# MercurialSDR_PWR.net
KiCad netlist of a schematic drawn in Altium Designer
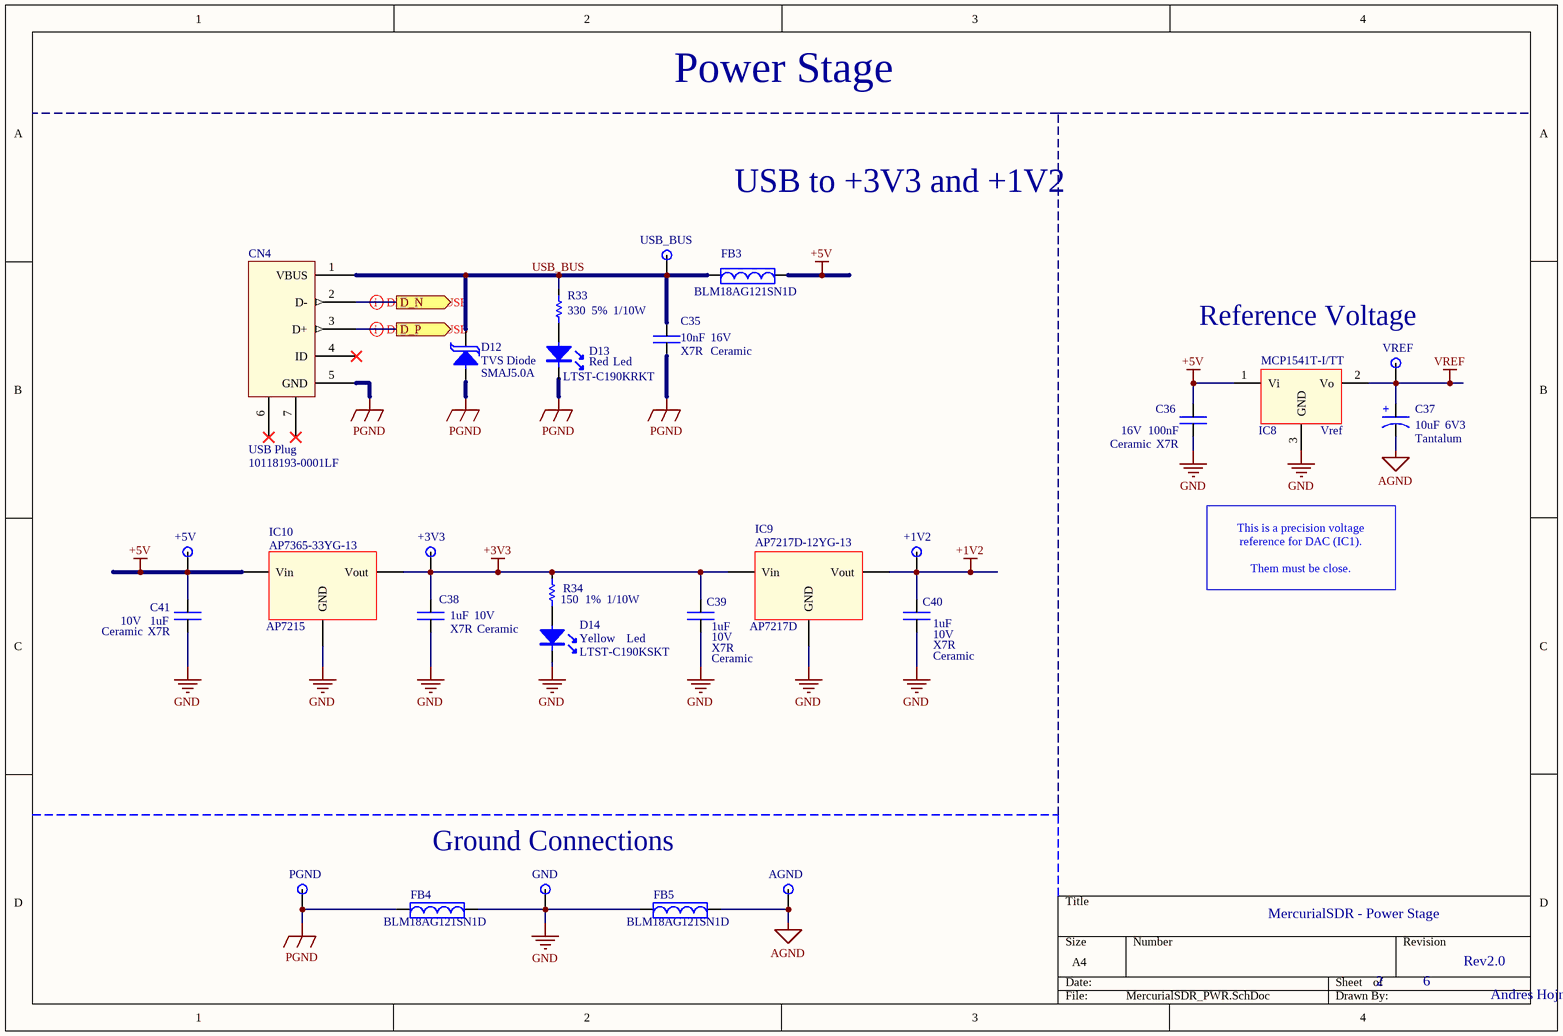
[diagram p0: MercurialSDR_PWR.SchDoc]

(export (version "E")
  (design (tool "Eeschema 10.0.6"))
  (components
    (comp (ref "C35")
      (value "10nF")
      (footprint "CAP_0603")
      (description "Capacitor no polarizado")
      (fields
        (field (name "TEMP COEF") "X7R")
        (field (name "PART NUMBER") "CC0603KRX7R7BB103")
        (field (name "VR") "16V")
        (field (name "MATERIAL") "Ceramic")
        (field (name "Comment") "Capacitor")
      )
      (libsource (lib "MercurialSDR") (part "Cap"))
    )
    (comp (ref "C36")
      (value "100nF")
      (footprint "CAP_0603")
      (description "Capacitor no polarizado")
      (fields
        (field (name "TEMP COEF") "X7R")
        (field (name "PART NUMBER") "CL10B104KO8NNNC")
        (field (name "VR") "16V")
        (field (name "MATERIAL") "Ceramic")
        (field (name "Comment") "Capacitor")
      )
      (libsource (lib "MercurialSDR") (part "Cap"))
    )
    (comp (ref "C37")
      (value "10uF")
      (footprint "CAP_TANT_1206")
      (description "Capacitor polarizado")
      (fields
        (field (name "PART NUMBER") "TAJA106K006RNJ")
        (field (name "VR") "6V3")
        (field (name "MATERIAL") "Tantalum")
        (field (name "Comment") "Capacitor Polarizado")
      )
      (libsource (lib "MercurialSDR") (part "Cap Pol"))
    )
    (comp (ref "C38")
      (value "1uF")
      (footprint "CAP_0603")
      (description "Capacitor no polarizado")
      (fields
        (field (name "TEMP COEF") "X7R")
        (field (name "PART NUMBER") "CL10B105KP8NNNC")
        (field (name "VR") "10V")
        (field (name "MATERIAL") "Ceramic")
        (field (name "Comment") "Capacitor")
      )
      (libsource (lib "MercurialSDR") (part "Cap"))
    )
    (comp (ref "C39")
      (value "1uF")
      (footprint "CAP_0603")
      (description "Capacitor no polarizado")
      (fields
        (field (name "TEMP COEF") "X7R")
        (field (name "PART NUMBER") "CL10B105KP8NNNC")
        (field (name "VR") "10V")
        (field (name "MATERIAL") "Ceramic")
        (field (name "Comment") "Capacitor")
      )
      (libsource (lib "MercurialSDR") (part "Cap"))
    )
    (comp (ref "C40")
      (value "1uF")
      (footprint "CAP_0603")
      (description "Capacitor no polarizado")
      (fields
        (field (name "TEMP COEF") "X7R")
        (field (name "PART NUMBER") "CL10B105KP8NNNC")
        (field (name "VR") "10V")
        (field (name "MATERIAL") "Ceramic")
        (field (name "Comment") "Capacitor")
      )
      (libsource (lib "MercurialSDR") (part "Cap"))
    )
    (comp (ref "C41")
      (value "1uF")
      (footprint "CAP_0603")
      (description "Capacitor no polarizado")
      (fields
        (field (name "TEMP COEF") "X7R")
        (field (name "PART NUMBER") "CL10B105KP8NNNC")
        (field (name "VR") "10V")
        (field (name "MATERIAL") "Ceramic")
        (field (name "Comment") "Capacitor")
      )
      (libsource (lib "MercurialSDR") (part "Cap"))
    )
    (comp (ref "CN4")
      (value "USB Plug")
      (footprint "USB_Micro")
      (fields (field (name "PART NUMBER") "10118193-0001LF"))
      (libsource (lib "MercurialSDR") (part "USB Plug"))
    )
    (comp (ref "D12")
      (value "TVS Diode")
      (footprint "DO-214AC")
      (description "TVS (Supresor de transitorios)")
      (fields (field (name "PART NUMBER") "SMAJ5.0A"))
      (libsource (lib "MercurialSDR") (part "TVS_DIODE"))
    )
    (comp (ref "D13")
      (value "Led")
      (footprint "LED_0603")
      (fields (field (name "COLOR") "Red") (field (name "PART NUMBER") "LTST-C190KRKT"))
      (libsource (lib "MercurialSDR") (part "Led"))
    )
    (comp (ref "D14")
      (value "Led")
      (footprint "LED_0603")
      (fields (field (name "COLOR") "Yellow") (field (name "PART NUMBER") "LTST-C190KSKT"))
      (libsource (lib "MercurialSDR") (part "Led"))
    )
    (comp (ref "FB3")
      (value "Ferrite Bead")
      (footprint "FERRITE_BEAD_0603")
      (fields (field (name "PART NUMBER") "BLM18AG121SN1D"))
      (libsource (lib "MercurialSDR") (part "Ferrite Bead"))
    )
    (comp (ref "FB4")
      (value "Ferrite Bead")
      (footprint "FERRITE_BEAD_0603")
      (fields (field (name "PART NUMBER") "BLM18AG121SN1D"))
      (libsource (lib "MercurialSDR") (part "Ferrite Bead"))
    )
    (comp (ref "FB5")
      (value "Ferrite Bead")
      (footprint "FERRITE_BEAD_0603")
      (fields (field (name "PART NUMBER") "BLM18AG121SN1D"))
      (libsource (lib "MercurialSDR") (part "Ferrite Bead"))
    )
    (comp (ref "IC8")
      (value "Vref")
      (footprint "SOT-23-3")
      (description "Reference Voltage")
      (fields (field (name "PART NUMBER") "MCP1541T-I/TT"))
      (libsource (lib "MercurialSDR") (part "MCP1541"))
    )
    (comp (ref "IC9")
      (value "AP7217D")
      (footprint "SOT89-3L")
      (description "Linear Voltage Regulator 1V2")
      (fields (field (name "PART NUMBER") "AP7217D-12YG-13"))
      (libsource (lib "MercurialSDR") (part "AP7217D"))
    )
    (comp (ref "IC10")
      (value "AP7215")
      (footprint "SOT89-3L")
      (description "Linear Voltage Regulator 3v3")
      (fields (field (name "PART NUMBER") "AP7365-33YG-13"))
      (libsource (lib "MercurialSDR") (part "AP7215"))
    )
    (comp (ref "R33")
      (value "330")
      (footprint "RES_0603")
      (description "Resistor")
      (fields
        (field (name "POWER") "1/10W")
        (field (name "PART NUMBER") "CR0603-JW-331ELF")
        (field (name "TOLERANCE") "5%")
        (field (name "Comment") "Resistor SMD")
      )
      (libsource (lib "MercurialSDR") (part "Res"))
    )
    (comp (ref "R34")
      (value "150")
      (footprint "RES_0603")
      (description "Resistor")
      (fields
        (field (name "POWER") "1/10W")
        (field (name "PART NUMBER") "CR0603-FX-1500ELF")
        (field (name "TOLERANCE") "1%")
        (field (name "Comment") "Resistor SMD")
      )
      (libsource (lib "MercurialSDR") (part "Res"))
    )
    (comp (ref "TP9")
      (value "Test Point")
      (footprint "TP_TOP")
      (fields (field (name "TP NAME") "USB_BUS"))
      (libsource (lib "MercurialSDR") (part "Test Point"))
    )
    (comp (ref "TP10")
      (value "Test Point")
      (footprint "TP_TOP")
      (fields (field (name "TP NAME") "VREF"))
      (libsource (lib "MercurialSDR") (part "Test Point"))
    )
    (comp (ref "TP11")
      (value "Test Point")
      (footprint "TP_TOP")
      (fields (field (name "TP NAME") "+5V"))
      (libsource (lib "MercurialSDR") (part "Test Point"))
    )
    (comp (ref "TP12")
      (value "Test Point")
      (footprint "TP_TOP")
      (fields (field (name "TP NAME") "+3V3"))
      (libsource (lib "MercurialSDR") (part "Test Point"))
    )
    (comp (ref "TP13")
      (value "Test Point")
      (footprint "TP_TOP")
      (fields (field (name "TP NAME") "+1V2"))
      (libsource (lib "MercurialSDR") (part "Test Point"))
    )
    (comp (ref "TP14")
      (value "Test Point")
      (footprint "TP_TH")
      (fields (field (name "TP NAME") "PGND"))
      (libsource (lib "MercurialSDR") (part "Test Point"))
    )
    (comp (ref "TP15")
      (value "Test Point")
      (footprint "TP_TOP")
      (fields (field (name "TP NAME") "GND"))
      (libsource (lib "MercurialSDR") (part "Test Point"))
    )
    (comp (ref "TP16")
      (value "Test Point")
      (footprint "TP_TOP")
      (fields (field (name "TP NAME") "AGND"))
      (libsource (lib "MercurialSDR") (part "Test Point"))
    )
  )
  (nets
    (net (code "1") (name "+1V2") (class "Default")
      (node (ref "C40") (pin "1") (pinfunction "1_1") (pintype "passive"))
      (node (ref "IC9") (pin "3") (pinfunction "Vout_3") (pintype "passive"))
      (node (ref "TP13") (pin "1") (pinfunction "TP?_1") (pintype "passive"))
    )
    (net (code "2") (name "+3V3") (class "Default")
      (node (ref "C38") (pin "1") (pinfunction "1_1") (pintype "passive"))
      (node (ref "C39") (pin "1") (pinfunction "1_1") (pintype "passive"))
      (node (ref "IC10") (pin "1") (pinfunction "Vout_1") (pintype "passive"))
      (node (ref "IC9") (pin "2") (pinfunction "Vin_2") (pintype "passive"))
      (node (ref "R34") (pin "1") (pinfunction "1_1") (pintype "passive"))
      (node (ref "TP12") (pin "1") (pinfunction "TP?_1") (pintype "passive"))
    )
    (net (code "3") (name "+5V") (class "Default")
      (node (ref "C36") (pin "1") (pinfunction "1_1") (pintype "passive"))
      (node (ref "C41") (pin "1") (pinfunction "1_1") (pintype "passive"))
      (node (ref "FB3") (pin "2") (pinfunction "2_2") (pintype "passive"))
      (node (ref "IC10") (pin "3") (pinfunction "Vin_3") (pintype "passive"))
      (node (ref "IC8") (pin "1") (pinfunction "Vi_1") (pintype "passive"))
      (node (ref "TP11") (pin "1") (pinfunction "TP?_1") (pintype "passive"))
    )
    (net (code "4") (name "/D_N") (class "Default")
      (node (ref "CN4") (pin "2") (pinfunction "D-_2") (pintype "output"))
    )
    (net (code "5") (name "/D_P") (class "Default")
      (node (ref "CN4") (pin "3") (pinfunction "D+_3") (pintype "output"))
    )
    (net (code "6") (name "/USB_BUS") (class "Default")
      (node (ref "C35") (pin "1") (pinfunction "1_1") (pintype "passive"))
      (node (ref "CN4") (pin "1") (pinfunction "VBUS_1") (pintype "power_in"))
      (node (ref "D12") (pin "2") (pinfunction "K_2") (pintype "passive"))
      (node (ref "FB3") (pin "1") (pinfunction "1_1") (pintype "passive"))
      (node (ref "R33") (pin "1") (pinfunction "1_1") (pintype "passive"))
      (node (ref "TP9") (pin "1") (pinfunction "TP?_1") (pintype "passive"))
    )
    (net (code "7") (name "AGND") (class "Default")
      (node (ref "C37") (pin "2") (pinfunction "2_2") (pintype "passive"))
      (node (ref "FB5") (pin "2") (pinfunction "2_2") (pintype "passive"))
      (node (ref "TP16") (pin "1") (pinfunction "TP?_1") (pintype "passive"))
    )
    (net (code "8") (name "GND") (class "Default")
      (node (ref "C36") (pin "2") (pinfunction "2_2") (pintype "passive"))
      (node (ref "C38") (pin "2") (pinfunction "2_2") (pintype "passive"))
      (node (ref "C39") (pin "2") (pinfunction "2_2") (pintype "passive"))
      (node (ref "C40") (pin "2") (pinfunction "2_2") (pintype "passive"))
      (node (ref "C41") (pin "2") (pinfunction "2_2") (pintype "passive"))
      (node (ref "D14") (pin "2") (pinfunction "K_2") (pintype "passive"))
      (node (ref "FB4") (pin "2") (pinfunction "2_2") (pintype "passive"))
      (node (ref "FB5") (pin "1") (pinfunction "1_1") (pintype "passive"))
      (node (ref "IC10") (pin "2") (pinfunction "GND_2") (pintype "passive"))
      (node (ref "IC8") (pin "3") (pinfunction "GND_3") (pintype "passive"))
      (node (ref "IC9") (pin "1") (pinfunction "GND_1") (pintype "passive"))
      (node (ref "TP15") (pin "1") (pinfunction "TP?_1") (pintype "passive"))
    )
    (net (code "9") (name "Net-(D13-A)") (class "Default")
      (node (ref "D13") (pin "1") (pinfunction "A_1") (pintype "passive"))
      (node (ref "R33") (pin "2") (pinfunction "2_2") (pintype "passive"))
    )
    (net (code "10") (name "Net-(D14-A)") (class "Default")
      (node (ref "D14") (pin "1") (pinfunction "A_1") (pintype "passive"))
      (node (ref "R34") (pin "2") (pinfunction "2_2") (pintype "passive"))
    )
    (net (code "11") (name "PGND") (class "Default")
      (node (ref "C35") (pin "2") (pinfunction "2_2") (pintype "passive"))
      (node (ref "CN4") (pin "5") (pinfunction "GND_5") (pintype "power_in"))
      (node (ref "D12") (pin "1") (pinfunction "A_1") (pintype "passive"))
      (node (ref "D13") (pin "2") (pinfunction "K_2") (pintype "passive"))
      (node (ref "FB4") (pin "1") (pinfunction "1_1") (pintype "passive"))
      (node (ref "TP14") (pin "1") (pinfunction "TP?_1") (pintype "passive"))
    )
    (net (code "12") (name "VREF") (class "Default")
      (node (ref "C37") (pin "1") (pinfunction "1_1") (pintype "passive"))
      (node (ref "IC8") (pin "2") (pinfunction "Vo_2") (pintype "passive"))
      (node (ref "TP10") (pin "1") (pinfunction "TP?_1") (pintype "passive"))
    )
    (net (code "13") (name "unconnected-(CN4-ID-Pad4)") (class "Default")
      (node (ref "CN4") (pin "4") (pinfunction "ID_4") (pintype "power_in+no_connect"))
    )
    (net (code "14") (name "unconnected-(CN4-Shield-Pad6)") (class "Default")
      (node (ref "CN4") (pin "6") (pinfunction "Shield_6") (pintype "passive+no_connect"))
    )
    (net (code "15") (name "unconnected-(CN4-Shield-Pad7)") (class "Default")
      (node (ref "CN4") (pin "7") (pinfunction "Shield_7") (pintype "passive+no_connect"))
    )
  )
)
